# RFID_PCB_DONE.net
KiCad netlist of a schematic drawn in EAGLE
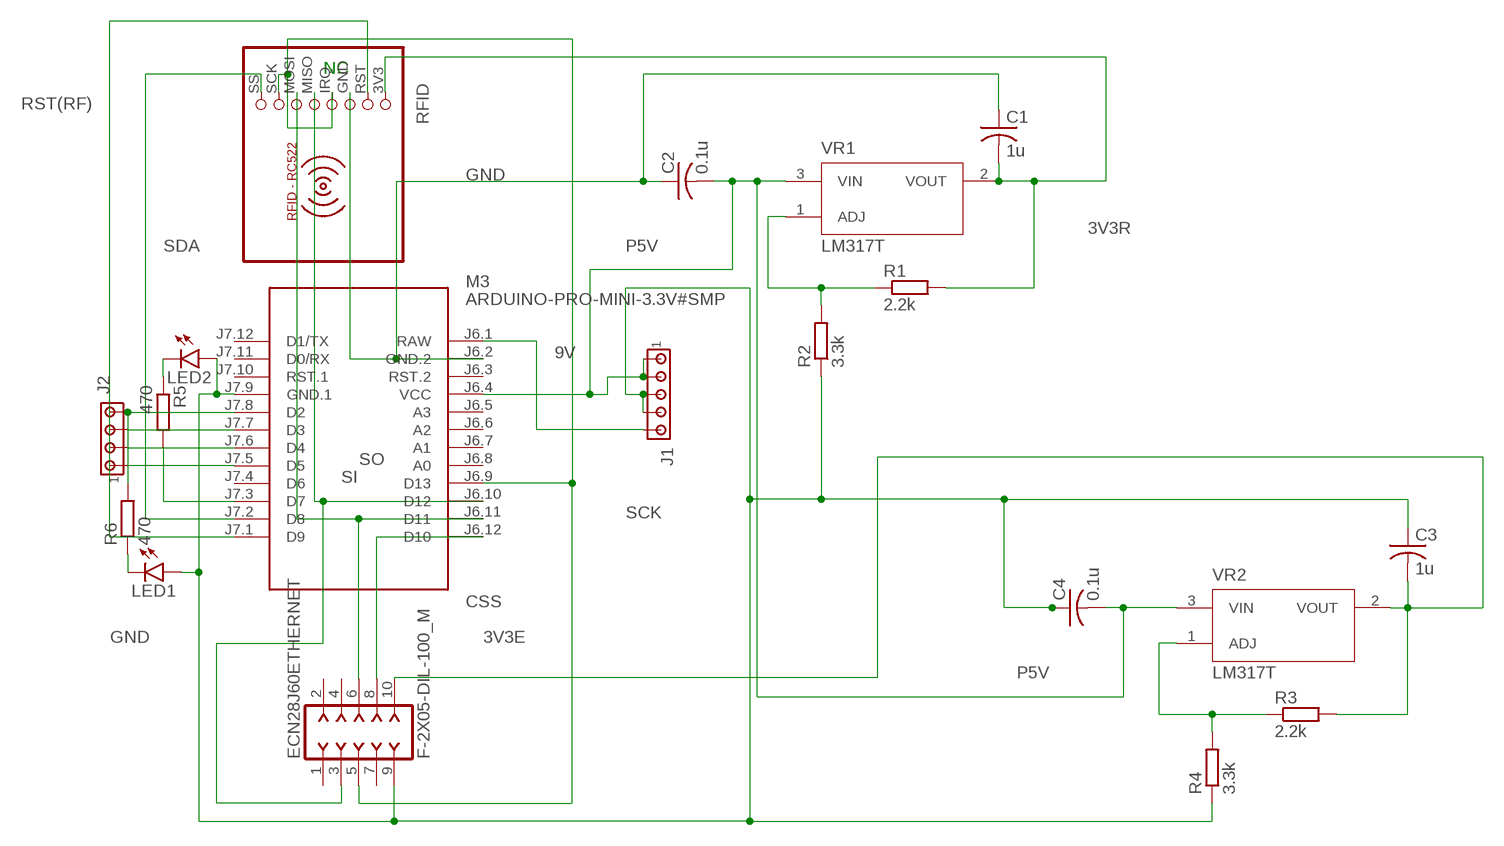
[diagram p0: schematic, sheet 1]

(export (version "E")
  (design (tool "Eeschema 10.0.6"))
  (components
    (comp (ref "C1")
      (value "1u")
      (footprint "eagle-import:C025-025X050")
      (libsource (lib "eagle-import") (part "C-US025-025X050"))
    )
    (comp (ref "C2")
      (value "0.1u")
      (footprint "eagle-import:C025-025X050")
      (libsource (lib "eagle-import") (part "C-US025-025X050"))
    )
    (comp (ref "C3")
      (value "1u")
      (footprint "eagle-import:C025-025X050")
      (libsource (lib "eagle-import") (part "C-US025-025X050"))
    )
    (comp (ref "C4")
      (value "0.1u")
      (footprint "eagle-import:C025-025X050")
      (libsource (lib "eagle-import") (part "C-US025-025X050"))
    )
    (comp (ref "ECN28J60ETHERNET")
      (value "F-2X05-DIL-100_M")
      (footprint "eagle-import:DIL-100-2X05_M")
      (libsource (lib "eagle-import") (part "F-2X05-DIL-100_M"))
    )
    (comp (ref "J1")
      (value "MTA05-100")
      (footprint "eagle-import:10X05MTA")
      (libsource (lib "eagle-import") (part "MTA05-100"))
    )
    (comp (ref "J2")
      (value "MTA04-100")
      (footprint "eagle-import:10X04MTA")
      (libsource (lib "eagle-import") (part "MTA04-100"))
    )
    (comp (ref "LED1")
      (value "LED3MM")
      (footprint "eagle-import:LED3MM")
      (libsource (lib "eagle-import") (part "LED3MM"))
    )
    (comp (ref "LED2")
      (value "LED3MM")
      (footprint "eagle-import:LED3MM")
      (libsource (lib "eagle-import") (part "LED3MM"))
    )
    (comp (ref "M3")
      (value "ARDUINO-PRO-MINI-3.3V#SMP")
      (footprint "eagle-import:ARDUINO-PRO-MINI#SMP")
      (libsource (lib "eagle-import") (part "ARDUINO-PRO-MINI-#SMP3.3V"))
    )
    (comp (ref "R1")
      (value "2.2k")
      (footprint "eagle-import:0207_10")
      (libsource (lib "eagle-import") (part "R-EU_0207/10"))
    )
    (comp (ref "R2")
      (value "3.3k")
      (footprint "eagle-import:0207_10")
      (libsource (lib "eagle-import") (part "R-EU_0207/10"))
    )
    (comp (ref "R3")
      (value "2.2k")
      (footprint "eagle-import:0207_10")
      (libsource (lib "eagle-import") (part "R-EU_0207/10"))
    )
    (comp (ref "R4")
      (value "3.3k")
      (footprint "eagle-import:0207_10")
      (libsource (lib "eagle-import") (part "R-EU_0207/10"))
    )
    (comp (ref "R5")
      (value "470")
      (footprint "eagle-import:0207_10")
      (libsource (lib "eagle-import") (part "R-EU_0207/10"))
    )
    (comp (ref "R6")
      (value "470")
      (footprint "eagle-import:0207_10")
      (libsource (lib "eagle-import") (part "R-EU_0207/10"))
    )
    (comp (ref "RFID")
      (value "RFID-RC522")
      (footprint "eagle-import:RFID-RC522")
      (libsource (lib "eagle-import") (part "RFID-RC522"))
    )
    (comp (ref "VR1")
      (value "LM317T")
      (footprint "eagle-import:TO254P1054X470X1955-3")
      (fields (field (name "MF") "Texas Instruments"))
      (libsource (lib "eagle-import") (part "LM317T"))
    )
    (comp (ref "VR2")
      (value "LM317T")
      (footprint "eagle-import:TO254P1054X470X1955-3")
      (fields (field (name "MF") "Texas Instruments"))
      (libsource (lib "eagle-import") (part "LM317T"))
    )
  )
  (nets
    (net (code "1") (name "/3V3E") (class "Default")
      (node (ref "C3") (pin "2") (pinfunction "2_2") (pintype "passive"))
      (node (ref "ECN28J60ETHERNET") (pin "10") (pinfunction "10_10") (pintype "passive"))
      (node (ref "R3") (pin "2") (pinfunction "2_2") (pintype "passive"))
      (node (ref "VR2") (pin "2") (pinfunction "VOUT_2") (pintype "output"))
    )
    (net (code "2") (name "/3V3R") (class "Default")
      (node (ref "C1") (pin "2") (pinfunction "2_2") (pintype "passive"))
      (node (ref "R1") (pin "2") (pinfunction "2_2") (pintype "passive"))
      (node (ref "RFID") (pin "3V3") (pinfunction "1_3V3") (pintype "passive"))
      (node (ref "VR1") (pin "2") (pinfunction "VOUT_2") (pintype "output"))
    )
    (net (code "3") (name "/9V") (class "Default")
      (node (ref "J1") (pin "5") (pinfunction "5_5") (pintype "passive"))
      (node (ref "M3") (pin "J6.1") (pinfunction "RAW_J6.1") (pintype "power_in"))
    )
    (net (code "4") (name "/CSS") (class "Default")
      (node (ref "ECN28J60ETHERNET") (pin "8") (pinfunction "8_8") (pintype "passive"))
      (node (ref "M3") (pin "J6.12") (pinfunction "D10_J6.12") (pintype "bidirectional"))
    )
    (net (code "5") (name "/GND") (class "Default")
      (node (ref "C1") (pin "1") (pinfunction "1_1") (pintype "passive"))
      (node (ref "C2") (pin "1") (pinfunction "1_1") (pintype "passive"))
      (node (ref "C3") (pin "1") (pinfunction "1_1") (pintype "passive"))
      (node (ref "C4") (pin "1") (pinfunction "1_1") (pintype "passive"))
      (node (ref "ECN28J60ETHERNET") (pin "9") (pinfunction "9_9") (pintype "passive"))
      (node (ref "J1") (pin "3") (pinfunction "3_3") (pintype "passive"))
      (node (ref "J1") (pin "4") (pinfunction "4_4") (pintype "passive"))
      (node (ref "LED1") (pin "A") (pinfunction "A_A") (pintype "passive"))
      (node (ref "LED2") (pin "A") (pinfunction "A_A") (pintype "passive"))
      (node (ref "M3") (pin "J6.2") (pinfunction "GND.2_J6.2") (pintype "power_in"))
      (node (ref "M3") (pin "J7.9") (pinfunction "GND.1_J7.9") (pintype "power_in"))
      (node (ref "R2") (pin "1") (pinfunction "1_1") (pintype "passive"))
      (node (ref "R4") (pin "1") (pinfunction "1_1") (pintype "passive"))
      (node (ref "RFID") (pin "GND") (pinfunction "3_GND") (pintype "passive"))
    )
    (net (code "6") (name "/P5V") (class "Default")
      (node (ref "C2") (pin "2") (pinfunction "2_2") (pintype "passive"))
      (node (ref "C4") (pin "2") (pinfunction "2_2") (pintype "passive"))
      (node (ref "J1") (pin "1") (pinfunction "1_1") (pintype "passive"))
      (node (ref "J1") (pin "2") (pinfunction "2_2") (pintype "passive"))
      (node (ref "M3") (pin "J6.4") (pinfunction "VCC_J6.4") (pintype "power_in"))
      (node (ref "VR1") (pin "3") (pinfunction "VIN_3") (pintype "input"))
      (node (ref "VR2") (pin "3") (pinfunction "VIN_3") (pintype "input"))
    )
    (net (code "7") (name "/RST(RF)") (class "Default")
      (node (ref "M3") (pin "J7.1") (pinfunction "D9_J7.1") (pintype "bidirectional"))
      (node (ref "RFID") (pin "RST") (pinfunction "2_RST") (pintype "passive"))
    )
    (net (code "8") (name "/SCK") (class "Default")
      (node (ref "ECN28J60ETHERNET") (pin "5") (pinfunction "5_5") (pintype "passive"))
      (node (ref "M3") (pin "J6.9") (pinfunction "D13_J6.9") (pintype "bidirectional"))
      (node (ref "RFID") (pin "IRQ") (pinfunction "4_IRQ") (pintype "passive"))
      (node (ref "RFID") (pin "SCK") (pinfunction "7_SCK") (pintype "passive"))
    )
    (net (code "9") (name "/SDA") (class "Default")
      (node (ref "M3") (pin "J7.2") (pinfunction "D8_J7.2") (pintype "bidirectional"))
      (node (ref "RFID") (pin "SS") (pinfunction "8_SS") (pintype "passive"))
    )
    (net (code "10") (name "/SI") (class "Default")
      (node (ref "ECN28J60ETHERNET") (pin "6") (pinfunction "6_6") (pintype "passive"))
      (node (ref "M3") (pin "J6.11") (pinfunction "D11_J6.11") (pintype "bidirectional"))
      (node (ref "RFID") (pin "MOSI") (pinfunction "6_MOSI") (pintype "passive"))
    )
    (net (code "11") (name "/SO") (class "Default")
      (node (ref "ECN28J60ETHERNET") (pin "3") (pinfunction "3_3") (pintype "passive"))
      (node (ref "M3") (pin "J6.10") (pinfunction "D12_J6.10") (pintype "bidirectional"))
      (node (ref "RFID") (pin "MISO") (pinfunction "5_MISO") (pintype "passive"))
    )
    (net (code "12") (name "Net-(LED1-C)") (class "Default")
      (node (ref "LED1") (pin "K") (pinfunction "C_K") (pintype "passive"))
      (node (ref "R6") (pin "1") (pinfunction "1_1") (pintype "passive"))
    )
    (net (code "13") (name "Net-(LED2-C)") (class "Default")
      (node (ref "LED2") (pin "K") (pinfunction "C_K") (pintype "passive"))
      (node (ref "R5") (pin "1") (pinfunction "1_1") (pintype "passive"))
    )
    (net (code "14") (name "Net-(M3-D2)") (class "Default")
      (node (ref "J2") (pin "4") (pinfunction "4_4") (pintype "passive"))
      (node (ref "M3") (pin "J7.8") (pinfunction "D2_J7.8") (pintype "bidirectional"))
      (node (ref "R6") (pin "2") (pinfunction "2_2") (pintype "passive"))
    )
    (net (code "15") (name "Net-(M3-D3)") (class "Default")
      (node (ref "J2") (pin "3") (pinfunction "3_3") (pintype "passive"))
      (node (ref "M3") (pin "J7.7") (pinfunction "D3_J7.7") (pintype "bidirectional"))
    )
    (net (code "16") (name "Net-(M3-D4)") (class "Default")
      (node (ref "J2") (pin "2") (pinfunction "2_2") (pintype "passive"))
      (node (ref "M3") (pin "J7.6") (pinfunction "D4_J7.6") (pintype "bidirectional"))
    )
    (net (code "17") (name "Net-(M3-D5)") (class "Default")
      (node (ref "J2") (pin "1") (pinfunction "1_1") (pintype "passive"))
      (node (ref "M3") (pin "J7.5") (pinfunction "D5_J7.5") (pintype "bidirectional"))
    )
    (net (code "18") (name "Net-(M3-D7)") (class "Default")
      (node (ref "M3") (pin "J7.3") (pinfunction "D7_J7.3") (pintype "bidirectional"))
      (node (ref "R5") (pin "2") (pinfunction "2_2") (pintype "passive"))
    )
    (net (code "19") (name "Net-(VR1-ADJ)") (class "Default")
      (node (ref "R1") (pin "1") (pinfunction "1_1") (pintype "passive"))
      (node (ref "R2") (pin "2") (pinfunction "2_2") (pintype "passive"))
      (node (ref "VR1") (pin "1") (pinfunction "ADJ_1") (pintype "input"))
    )
    (net (code "20") (name "Net-(VR2-ADJ)") (class "Default")
      (node (ref "R3") (pin "1") (pinfunction "1_1") (pintype "passive"))
      (node (ref "R4") (pin "2") (pinfunction "2_2") (pintype "passive"))
      (node (ref "VR2") (pin "1") (pinfunction "ADJ_1") (pintype "input"))
    )
    (net (code "21") (name "unconnected-(ECN28J60ETHERNET-Pad1)") (class "Default")
      (node (ref "ECN28J60ETHERNET") (pin "1") (pinfunction "1_1") (pintype "passive"))
    )
    (net (code "22") (name "unconnected-(ECN28J60ETHERNET-Pad2)") (class "Default")
      (node (ref "ECN28J60ETHERNET") (pin "2") (pinfunction "2_2") (pintype "passive"))
    )
    (net (code "23") (name "unconnected-(ECN28J60ETHERNET-Pad4)") (class "Default")
      (node (ref "ECN28J60ETHERNET") (pin "4") (pinfunction "4_4") (pintype "passive"))
    )
    (net (code "24") (name "unconnected-(ECN28J60ETHERNET-Pad7)") (class "Default")
      (node (ref "ECN28J60ETHERNET") (pin "7") (pinfunction "7_7") (pintype "passive"))
    )
    (net (code "25") (name "unconnected-(M3-A0-PadJ6.8)") (class "Default")
      (node (ref "M3") (pin "J6.8") (pinfunction "A0_J6.8") (pintype "bidirectional"))
    )
    (net (code "26") (name "unconnected-(M3-A1-PadJ6.7)") (class "Default")
      (node (ref "M3") (pin "J6.7") (pinfunction "A1_J6.7") (pintype "bidirectional"))
    )
    (net (code "27") (name "unconnected-(M3-A2-PadJ6.6)") (class "Default")
      (node (ref "M3") (pin "J6.6") (pinfunction "A2_J6.6") (pintype "bidirectional"))
    )
    (net (code "28") (name "unconnected-(M3-A3-PadJ6.5)") (class "Default")
      (node (ref "M3") (pin "J6.5") (pinfunction "A3_J6.5") (pintype "bidirectional"))
    )
    (net (code "29") (name "unconnected-(M3-D0{slash}RX-PadJ7.11)") (class "Default")
      (node (ref "M3") (pin "J7.11") (pinfunction "D0/RX_J7.11") (pintype "bidirectional"))
    )
    (net (code "30") (name "unconnected-(M3-D1{slash}TX-PadJ7.12)") (class "Default")
      (node (ref "M3") (pin "J7.12") (pinfunction "D1/TX_J7.12") (pintype "bidirectional"))
    )
    (net (code "31") (name "unconnected-(M3-D6-PadJ7.4)") (class "Default")
      (node (ref "M3") (pin "J7.4") (pinfunction "D6_J7.4") (pintype "bidirectional"))
    )
    (net (code "32") (name "unconnected-(M3-RST.1-PadJ7.10)") (class "Default")
      (node (ref "M3") (pin "J7.10") (pinfunction "RST.1_J7.10") (pintype "bidirectional"))
    )
    (net (code "33") (name "unconnected-(M3-RST.2-PadJ6.3)") (class "Default")
      (node (ref "M3") (pin "J6.3") (pinfunction "RST.2_J6.3") (pintype "bidirectional"))
    )
  )
)
